# Cap_Touch.net
KiCad netlist of a schematic drawn in EAGLE
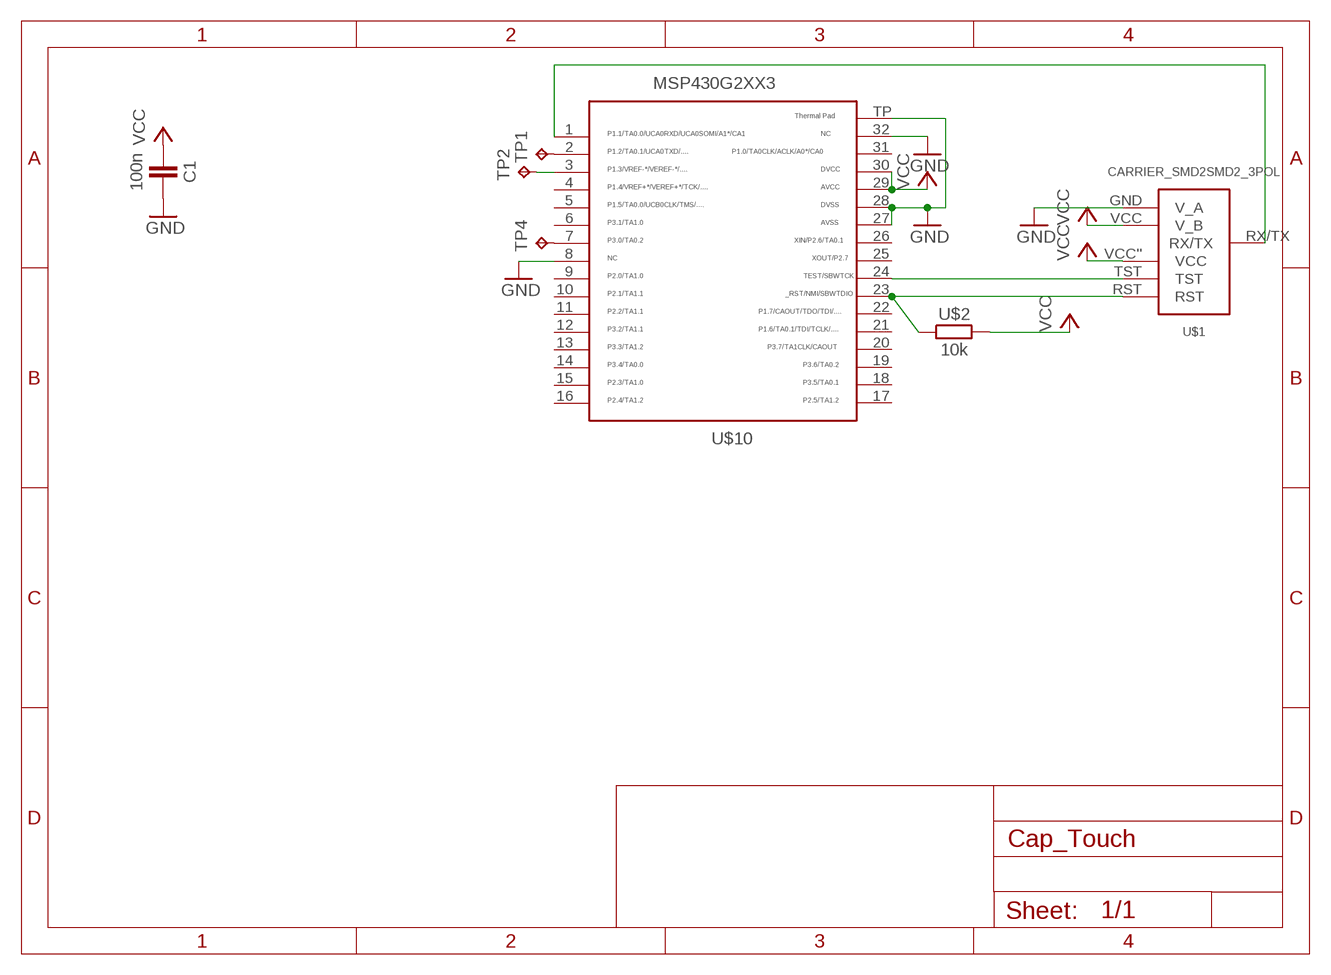
[diagram p0: schematic, sheet 1]

(export (version "E")
  (design (tool "Eeschema 10.0.6"))
  (components
    (comp (ref "C1")
      (value "100n")
      (footprint "eagle-import:603")
      (libsource (lib "eagle-import") (part "CAPACITOR"))
    )
    (comp (ref "TP1")
      (value "TPTP06R")
      (footprint "eagle-import:TP06R")
      (libsource (lib "eagle-import") (part "TPTP06R"))
    )
    (comp (ref "TP2")
      (value "TPTP06R")
      (footprint "eagle-import:TP06R")
      (libsource (lib "eagle-import") (part "TPTP06R"))
    )
    (comp (ref "TP4")
      (value "TPTP06R")
      (footprint "eagle-import:TP06R")
      (libsource (lib "eagle-import") (part "TPTP06R"))
    )
    (comp (ref "U$1")
      (value "CARRIER_SMD2SMD2_3POL")
      (footprint "eagle-import:CARRIER_SMD2_3POL")
      (libsource (lib "eagle-import") (part "CARRIER_SMD2SMD2_3POL"))
    )
    (comp (ref "U$2")
      (value "10k")
      (footprint "eagle-import:603")
      (libsource (lib "eagle-import") (part "RESISTOR0603"))
    )
    (comp (ref "U$10")
      (value "MSP430G2553")
      (footprint "eagle-import:QFN32")
      (libsource (lib "eagle-import") (part "MSP430G2553"))
    )
  )
  (nets
    (net (code "1") (name "GND") (class "Default")
      (node (ref "C1") (pin "2") (pinfunction "2_2") (pintype "passive"))
      (node (ref "U$1") (pin "GND") (pinfunction "V_A_GND") (pintype "bidirectional"))
      (node (ref "U$10") (pin "27") (pinfunction "27_27") (pintype "bidirectional"))
      (node (ref "U$10") (pin "28") (pinfunction "28_28") (pintype "bidirectional"))
      (node (ref "U$10") (pin "32") (pinfunction "32_32") (pintype "bidirectional"))
      (node (ref "U$10") (pin "8") (pinfunction "8_8") (pintype "bidirectional"))
      (node (ref "U$10") (pin "TP") (pinfunction "TP_TP") (pintype "bidirectional"))
    )
    (net (code "2") (name "Net-(TP1-PadTP)") (class "Default")
      (node (ref "TP1") (pin "TP") (pinfunction "TP_TP") (pintype "input"))
      (node (ref "U$10") (pin "2") (pinfunction "2_2") (pintype "bidirectional"))
    )
    (net (code "3") (name "Net-(TP2-PadTP)") (class "Default")
      (node (ref "TP2") (pin "TP") (pinfunction "TP_TP") (pintype "input"))
      (node (ref "U$10") (pin "3") (pinfunction "3_3") (pintype "bidirectional"))
    )
    (net (code "4") (name "Net-(TP4-PadTP)") (class "Default")
      (node (ref "TP4") (pin "TP") (pinfunction "TP_TP") (pintype "input"))
      (node (ref "U$10") (pin "7") (pinfunction "7_7") (pintype "bidirectional"))
    )
    (net (code "5") (name "Net-(U$1-PadRST)") (class "Default")
      (node (ref "U$1") (pin "RST") (pinfunction "RST_RST") (pintype "bidirectional"))
      (node (ref "U$10") (pin "23") (pinfunction "23_23") (pintype "bidirectional"))
      (node (ref "U$2") (pin "1") (pinfunction "1_1") (pintype "passive"))
    )
    (net (code "6") (name "Net-(U$1-PadRX{slash}TX)") (class "Default")
      (node (ref "U$1") (pin "RX/TX") (pinfunction "RX/TX_RX/TX") (pintype "bidirectional"))
      (node (ref "U$10") (pin "1") (pinfunction "1_1") (pintype "bidirectional"))
    )
    (net (code "7") (name "Net-(U$1-PadTST)") (class "Default")
      (node (ref "U$1") (pin "TST") (pinfunction "TST_TST") (pintype "bidirectional"))
      (node (ref "U$10") (pin "24") (pinfunction "24_24") (pintype "bidirectional"))
    )
    (net (code "8") (name "VCC") (class "Default")
      (node (ref "C1") (pin "1") (pinfunction "1_1") (pintype "passive"))
      (node (ref "U$1") (pin "VCC") (pinfunction "V_B_VCC") (pintype "bidirectional"))
      (node (ref "U$1") (pin "VCC''") (pinfunction "VCC_VCC''") (pintype "bidirectional"))
      (node (ref "U$10") (pin "29") (pinfunction "29_29") (pintype "bidirectional"))
      (node (ref "U$10") (pin "30") (pinfunction "30_30") (pintype "bidirectional"))
      (node (ref "U$2") (pin "2") (pinfunction "2_2") (pintype "passive"))
    )
    (net (code "9") (name "unconnected-(U$10-Pad4)") (class "Default")
      (node (ref "U$10") (pin "4") (pinfunction "4_4") (pintype "bidirectional"))
    )
    (net (code "10") (name "unconnected-(U$10-Pad5)") (class "Default")
      (node (ref "U$10") (pin "5") (pinfunction "5_5") (pintype "bidirectional"))
    )
    (net (code "11") (name "unconnected-(U$10-Pad6)") (class "Default")
      (node (ref "U$10") (pin "6") (pinfunction "6_6") (pintype "bidirectional"))
    )
    (net (code "12") (name "unconnected-(U$10-Pad9)") (class "Default")
      (node (ref "U$10") (pin "9") (pinfunction "9_9") (pintype "bidirectional"))
    )
    (net (code "13") (name "unconnected-(U$10-Pad10)") (class "Default")
      (node (ref "U$10") (pin "10") (pinfunction "10_10") (pintype "bidirectional"))
    )
    (net (code "14") (name "unconnected-(U$10-Pad11)") (class "Default")
      (node (ref "U$10") (pin "11") (pinfunction "11_11") (pintype "bidirectional"))
    )
    (net (code "15") (name "unconnected-(U$10-Pad12)") (class "Default")
      (node (ref "U$10") (pin "12") (pinfunction "12_12") (pintype "bidirectional"))
    )
    (net (code "16") (name "unconnected-(U$10-Pad13)") (class "Default")
      (node (ref "U$10") (pin "13") (pinfunction "13_13") (pintype "bidirectional"))
    )
    (net (code "17") (name "unconnected-(U$10-Pad14)") (class "Default")
      (node (ref "U$10") (pin "14") (pinfunction "14_14") (pintype "bidirectional"))
    )
    (net (code "18") (name "unconnected-(U$10-Pad15)") (class "Default")
      (node (ref "U$10") (pin "15") (pinfunction "15_15") (pintype "bidirectional"))
    )
    (net (code "19") (name "unconnected-(U$10-Pad16)") (class "Default")
      (node (ref "U$10") (pin "16") (pinfunction "16_16") (pintype "bidirectional"))
    )
    (net (code "20") (name "unconnected-(U$10-Pad17)") (class "Default")
      (node (ref "U$10") (pin "17") (pinfunction "17_17") (pintype "bidirectional"))
    )
    (net (code "21") (name "unconnected-(U$10-Pad18)") (class "Default")
      (node (ref "U$10") (pin "18") (pinfunction "18_18") (pintype "bidirectional"))
    )
    (net (code "22") (name "unconnected-(U$10-Pad19)") (class "Default")
      (node (ref "U$10") (pin "19") (pinfunction "19_19") (pintype "bidirectional"))
    )
    (net (code "23") (name "unconnected-(U$10-Pad20)") (class "Default")
      (node (ref "U$10") (pin "20") (pinfunction "20_20") (pintype "bidirectional"))
    )
    (net (code "24") (name "unconnected-(U$10-Pad21)") (class "Default")
      (node (ref "U$10") (pin "21") (pinfunction "21_21") (pintype "bidirectional"))
    )
    (net (code "25") (name "unconnected-(U$10-Pad22)") (class "Default")
      (node (ref "U$10") (pin "22") (pinfunction "22_22") (pintype "bidirectional"))
    )
    (net (code "26") (name "unconnected-(U$10-Pad25)") (class "Default")
      (node (ref "U$10") (pin "25") (pinfunction "25_25") (pintype "bidirectional"))
    )
    (net (code "27") (name "unconnected-(U$10-Pad26)") (class "Default")
      (node (ref "U$10") (pin "26") (pinfunction "26_26") (pintype "bidirectional"))
    )
    (net (code "28") (name "unconnected-(U$10-Pad31)") (class "Default")
      (node (ref "U$10") (pin "31") (pinfunction "31_31") (pintype "bidirectional"))
    )
  )
)
